# b3_bart_-_rev00.net
KiCad netlist of a schematic drawn in EAGLE
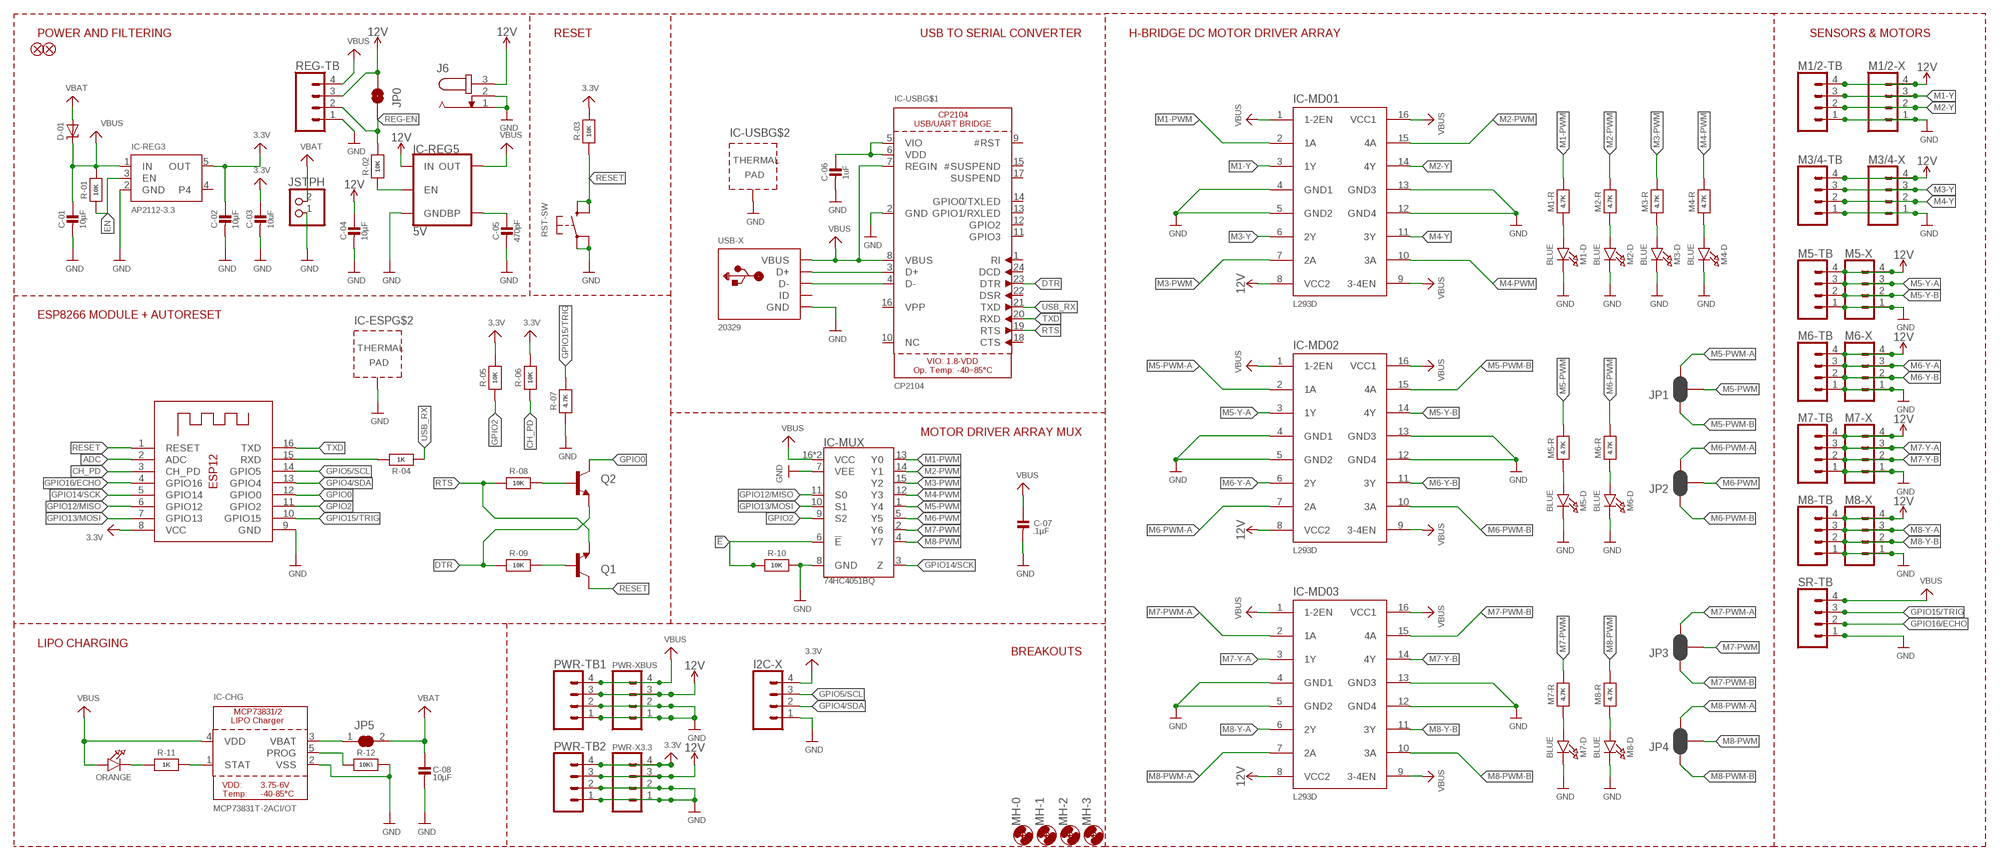
[diagram p0: schematic, sheet 1]

(export (version "E")
  (design (tool "Eeschema 10.0.6"))
  (components
    (comp (ref "C-01")
      (value "10µF")
      (footprint "eagle-import:0805-NO")
      (libsource (lib "eagle-import") (part "CAP_CERAMIC0805-NOOUTLINE"))
    )
    (comp (ref "C-02")
      (value "10µF")
      (footprint "eagle-import:0805-NO")
      (libsource (lib "eagle-import") (part "CAP_CERAMIC0805-NOOUTLINE"))
    )
    (comp (ref "C-03")
      (value "10uF")
      (footprint "eagle-import:0805-NO")
      (libsource (lib "eagle-import") (part "CAP_CERAMIC0805-NOOUTLINE"))
    )
    (comp (ref "C-04")
      (value "10µF")
      (footprint "eagle-import:0805-NO")
      (libsource (lib "eagle-import") (part "CAP_CERAMIC0805-NOOUTLINE"))
    )
    (comp (ref "C-05")
      (value "470pF")
      (footprint "eagle-import:0805-NO")
      (libsource (lib "eagle-import") (part "CAP_CERAMIC0805-NOOUTLINE"))
    )
    (comp (ref "C-06")
      (value "1uF")
      (footprint "eagle-import:0603-NO@1")
      (libsource (lib "eagle-import") (part "CAP_CERAMIC0603_NO"))
    )
    (comp (ref "C-07")
      (value ".1µF")
      (footprint "eagle-import:0805-NO")
      (libsource (lib "eagle-import") (part "CAP_CERAMIC0805-NOOUTLINE"))
    )
    (comp (ref "C-08")
      (value "10µF")
      (footprint "eagle-import:0805-NO")
      (libsource (lib "eagle-import") (part "CAP_CERAMIC0805-NOOUTLINE"))
    )
    (comp (ref "CHG-D")
      (value "ORANGE")
      (footprint "eagle-import:CHIPLED_0805_NOOUTLINE")
      (libsource (lib "eagle-import") (part "LED0805_NOOUTLINE"))
    )
    (comp (ref "D-01")
      (value "MBR120")
      (footprint "eagle-import:SOD-123")
      (libsource (lib "eagle-import") (part "DIODE-SCHOTTKYSOD-123"))
    )
    (comp (ref "FD1")
      (value "FIDUCIAL1X2")
      (footprint "eagle-import:FIDUCIAL-1X2")
      (libsource (lib "eagle-import") (part "FIDUCIAL1X2"))
    )
    (comp (ref "FD2")
      (value "FIDUCIAL1X2")
      (footprint "eagle-import:FIDUCIAL-1X2")
      (libsource (lib "eagle-import") (part "FIDUCIAL1X2"))
    )
    (comp (ref "I2C-X")
      (value "CONN_04LONGPADS")
      (footprint "eagle-import:1X04_LONGPADS")
      (libsource (lib "eagle-import") (part "CONN_04LONGPADS"))
    )
    (comp (ref "IC-CHG")
      (value "MCP73831T-2ACI/OT")
      (footprint "eagle-import:SOT23-5")
      (libsource (lib "eagle-import") (part "MCP73831/2"))
    )
    (comp (ref "IC-ESP")
      (value "ESP-12")
      (footprint "eagle-import:ESP-12S")
      (libsource (lib "eagle-import") (part "ESP-12S"))
    )
    (comp (ref "IC-MD01")
      (value "L293D")
      (footprint "eagle-import:DIL16")
      (libsource (lib "eagle-import") (part "L293D"))
    )
    (comp (ref "IC-MD02")
      (value "L293D")
      (footprint "eagle-import:DIL16")
      (libsource (lib "eagle-import") (part "L293D"))
    )
    (comp (ref "IC-MD03")
      (value "L293D")
      (footprint "eagle-import:DIL16")
      (libsource (lib "eagle-import") (part "L293D"))
    )
    (comp (ref "IC-MUX")
      (value "74HC4051BQ")
      (footprint "eagle-import:DHVQFN-16-2.5X3.5MM")
      (libsource (lib "eagle-import") (part "74HC4051BQ"))
    )
    (comp (ref "IC-REG3")
      (value "AP2112-3.3")
      (footprint "eagle-import:SOT23-5")
      (libsource (lib "eagle-import") (part "VREG_SOT23-5"))
    )
    (comp (ref "IC-REG5")
      (value "5V")
      (footprint "eagle-import:SOT23-5")
      (libsource (lib "eagle-import") (part "V_REG_MIC52055V"))
    )
    (comp (ref "IC-USB")
      (value "CP2104")
      (footprint "eagle-import:QFN24_4MM_SMSC")
      (libsource (lib "eagle-import") (part "CP2104"))
    )
    (comp (ref "J6")
      (value "JACK-PLUG1")
      (footprint "eagle-import:SPC4078")
      (libsource (lib "eagle-import") (part "JACK-PLUG1"))
    )
    (comp (ref "JP0")
      (value "JUMPER-SMT_2_NO_SILK")
      (footprint "eagle-import:SMT-JUMPER_2_NO_SILK")
      (libsource (lib "eagle-import") (part "JUMPER-SMT_2_NO_SILK"))
    )
    (comp (ref "JP1")
      (value "JUMPER-SMT_3_2-NC_PASTE_SILK")
      (footprint "eagle-import:SMT-JUMPER_3_2-NC_PASTE_SILK")
      (libsource (lib "eagle-import") (part "JUMPER-SMT_3_2-NC_PASTE_SILK"))
    )
    (comp (ref "JP2")
      (value "JUMPER-SMT_3_2-NC_PASTE_SILK")
      (footprint "eagle-import:SMT-JUMPER_3_2-NC_PASTE_SILK")
      (libsource (lib "eagle-import") (part "JUMPER-SMT_3_2-NC_PASTE_SILK"))
    )
    (comp (ref "JP3")
      (value "JUMPER-SMT_3_2-NC_PASTE_SILK")
      (footprint "eagle-import:SMT-JUMPER_3_2-NC_PASTE_SILK")
      (libsource (lib "eagle-import") (part "JUMPER-SMT_3_2-NC_PASTE_SILK"))
    )
    (comp (ref "JP4")
      (value "JUMPER-SMT_3_2-NC_PASTE_SILK")
      (footprint "eagle-import:SMT-JUMPER_3_2-NC_PASTE_SILK")
      (libsource (lib "eagle-import") (part "JUMPER-SMT_3_2-NC_PASTE_SILK"))
    )
    (comp (ref "JP5")
      (value "SOLDERJUMPER_CLOSED")
      (footprint "eagle-import:SOLDERJUMPER_CLOSEDWIRE")
      (libsource (lib "eagle-import") (part "SOLDERJUMPER_CLOSED"))
    )
    (comp (ref "M1-D")
      (value "BLUE")
      (footprint "eagle-import:CHIPLED_0805_NOOUTLINE")
      (libsource (lib "eagle-import") (part "LED0805_NOOUTLINE"))
    )
    (comp (ref "M1-R")
      (value "4.7K")
      (footprint "eagle-import:0603-NO")
      (libsource (lib "eagle-import") (part "RESISTOR_0603_NOOUT"))
    )
    (comp (ref "M1/2-TB")
      (value "CONN_04SCREW")
      (footprint "eagle-import:SCREWTERMINAL-3.5MM-4")
      (libsource (lib "eagle-import") (part "CONN_04SCREW"))
    )
    (comp (ref "M1/2-X")
      (value "CONN_04LONGPADS")
      (footprint "eagle-import:1X04_LONGPADS")
      (libsource (lib "eagle-import") (part "CONN_04LONGPADS"))
    )
    (comp (ref "M2-D")
      (value "BLUE")
      (footprint "eagle-import:CHIPLED_0805_NOOUTLINE")
      (libsource (lib "eagle-import") (part "LED0805_NOOUTLINE"))
    )
    (comp (ref "M2-R")
      (value "4.7K")
      (footprint "eagle-import:0603-NO")
      (libsource (lib "eagle-import") (part "RESISTOR_0603_NOOUT"))
    )
    (comp (ref "M3-D")
      (value "BLUE")
      (footprint "eagle-import:CHIPLED_0805_NOOUTLINE")
      (libsource (lib "eagle-import") (part "LED0805_NOOUTLINE"))
    )
    (comp (ref "M3-R")
      (value "4.7K")
      (footprint "eagle-import:0603-NO")
      (libsource (lib "eagle-import") (part "RESISTOR_0603_NOOUT"))
    )
    (comp (ref "M3/4-TB")
      (value "CONN_04SCREW")
      (footprint "eagle-import:SCREWTERMINAL-3.5MM-4")
      (libsource (lib "eagle-import") (part "CONN_04SCREW"))
    )
    (comp (ref "M3/4-X")
      (value "CONN_04LONGPADS")
      (footprint "eagle-import:1X04_LONGPADS")
      (libsource (lib "eagle-import") (part "CONN_04LONGPADS"))
    )
    (comp (ref "M4-D")
      (value "BLUE")
      (footprint "eagle-import:CHIPLED_0805_NOOUTLINE")
      (libsource (lib "eagle-import") (part "LED0805_NOOUTLINE"))
    )
    (comp (ref "M4-R")
      (value "4.7K")
      (footprint "eagle-import:0603-NO")
      (libsource (lib "eagle-import") (part "RESISTOR_0603_NOOUT"))
    )
    (comp (ref "M5-D")
      (value "BLUE")
      (footprint "eagle-import:CHIPLED_0805_NOOUTLINE")
      (libsource (lib "eagle-import") (part "LED0805_NOOUTLINE"))
    )
    (comp (ref "M5-R")
      (value "4.7K")
      (footprint "eagle-import:0603-NO")
      (libsource (lib "eagle-import") (part "RESISTOR_0603_NOOUT"))
    )
    (comp (ref "M5-TB")
      (value "CONN_04SCREW")
      (footprint "eagle-import:SCREWTERMINAL-3.5MM-4")
      (libsource (lib "eagle-import") (part "CONN_04SCREW"))
    )
    (comp (ref "M5-X")
      (value "CONN_04LONGPADS")
      (footprint "eagle-import:1X04_LONGPADS")
      (libsource (lib "eagle-import") (part "CONN_04LONGPADS"))
    )
    (comp (ref "M6-D")
      (value "BLUE")
      (footprint "eagle-import:CHIPLED_0805_NOOUTLINE")
      (libsource (lib "eagle-import") (part "LED0805_NOOUTLINE"))
    )
    (comp (ref "M6-R")
      (value "4.7K")
      (footprint "eagle-import:0603-NO")
      (libsource (lib "eagle-import") (part "RESISTOR_0603_NOOUT"))
    )
    (comp (ref "M6-TB")
      (value "CONN_04SCREW")
      (footprint "eagle-import:SCREWTERMINAL-3.5MM-4")
      (libsource (lib "eagle-import") (part "CONN_04SCREW"))
    )
    (comp (ref "M6-X")
      (value "CONN_04LONGPADS")
      (footprint "eagle-import:1X04_LONGPADS")
      (libsource (lib "eagle-import") (part "CONN_04LONGPADS"))
    )
    (comp (ref "M7-D")
      (value "BLUE")
      (footprint "eagle-import:CHIPLED_0805_NOOUTLINE")
      (libsource (lib "eagle-import") (part "LED0805_NOOUTLINE"))
    )
    (comp (ref "M7-R")
      (value "4.7K")
      (footprint "eagle-import:0603-NO")
      (libsource (lib "eagle-import") (part "RESISTOR_0603_NOOUT"))
    )
    (comp (ref "M7-TB")
      (value "CONN_04SCREW")
      (footprint "eagle-import:SCREWTERMINAL-3.5MM-4")
      (libsource (lib "eagle-import") (part "CONN_04SCREW"))
    )
    (comp (ref "M7-X")
      (value "CONN_04LONGPADS")
      (footprint "eagle-import:1X04_LONGPADS")
      (libsource (lib "eagle-import") (part "CONN_04LONGPADS"))
    )
    (comp (ref "M8-D")
      (value "BLUE")
      (footprint "eagle-import:CHIPLED_0805_NOOUTLINE")
      (libsource (lib "eagle-import") (part "LED0805_NOOUTLINE"))
    )
    (comp (ref "M8-R")
      (value "4.7K")
      (footprint "eagle-import:0603-NO")
      (libsource (lib "eagle-import") (part "RESISTOR_0603_NOOUT"))
    )
    (comp (ref "M8-TB")
      (value "CONN_04SCREW")
      (footprint "eagle-import:SCREWTERMINAL-3.5MM-4")
      (libsource (lib "eagle-import") (part "CONN_04SCREW"))
    )
    (comp (ref "M8-X")
      (value "CONN_04LONGPADS")
      (footprint "eagle-import:1X04_LONGPADS")
      (libsource (lib "eagle-import") (part "CONN_04LONGPADS"))
    )
    (comp (ref "MH-0")
      (value "MOUNT-HOLE3.0")
      (footprint "eagle-import:3,0")
      (libsource (lib "eagle-import") (part "MOUNT-HOLE3.0"))
    )
    (comp (ref "MH-1")
      (value "MOUNT-HOLE3.0")
      (footprint "eagle-import:3,0")
      (libsource (lib "eagle-import") (part "MOUNT-HOLE3.0"))
    )
    (comp (ref "MH-2")
      (value "MOUNT-HOLE3.0")
      (footprint "eagle-import:3,0")
      (libsource (lib "eagle-import") (part "MOUNT-HOLE3.0"))
    )
    (comp (ref "MH-3")
      (value "MOUNT-HOLE3.0")
      (footprint "eagle-import:3,0")
      (libsource (lib "eagle-import") (part "MOUNT-HOLE3.0"))
    )
    (comp (ref "PWR-TB1")
      (value "CONN_04SCREW")
      (footprint "eagle-import:SCREWTERMINAL-3.5MM-4")
      (libsource (lib "eagle-import") (part "CONN_04SCREW"))
    )
    (comp (ref "PWR-TB2")
      (value "CONN_04SCREW")
      (footprint "eagle-import:SCREWTERMINAL-3.5MM-4")
      (libsource (lib "eagle-import") (part "CONN_04SCREW"))
    )
    (comp (ref "PWR-X3.3")
      (value "CONN_04LONGPADS")
      (footprint "eagle-import:1X04_LONGPADS")
      (libsource (lib "eagle-import") (part "CONN_04LONGPADS"))
    )
    (comp (ref "PWR-XBUS")
      (value "CONN_04LONGPADS")
      (footprint "eagle-import:1X04_LONGPADS")
      (libsource (lib "eagle-import") (part "CONN_04LONGPADS"))
    )
    (comp (ref "Q1")
      (value "mmbt2222")
      (footprint "eagle-import:SOT23-3")
      (libsource (lib "eagle-import") (part "TRANSISTOR_NPNSOT23-3"))
    )
    (comp (ref "Q2")
      (value "mmbt2222")
      (footprint "eagle-import:SOT23-3")
      (libsource (lib "eagle-import") (part "TRANSISTOR_NPNSOT23-3"))
    )
    (comp (ref "R-01")
      (value "10K")
      (footprint "eagle-import:0603-NO")
      (libsource (lib "eagle-import") (part "RESISTOR_0603_NOOUT"))
    )
    (comp (ref "R-02")
      (value "10K")
      (footprint "eagle-import:0603-NO")
      (libsource (lib "eagle-import") (part "RESISTOR_0603_NOOUT"))
    )
    (comp (ref "R-03")
      (value "10K")
      (footprint "eagle-import:0603-NO")
      (libsource (lib "eagle-import") (part "RESISTOR_0603_NOOUT"))
    )
    (comp (ref "R-04")
      (value "1K")
      (footprint "eagle-import:_0603MP")
      (libsource (lib "eagle-import") (part "RESISTOR_0603MP"))
    )
    (comp (ref "R-05")
      (value "10K")
      (footprint "eagle-import:0603-NO")
      (libsource (lib "eagle-import") (part "RESISTOR_0603_NOOUT"))
    )
    (comp (ref "R-06")
      (value "10K")
      (footprint "eagle-import:0603-NO")
      (libsource (lib "eagle-import") (part "RESISTOR_0603_NOOUT"))
    )
    (comp (ref "R-07")
      (value "4.7K")
      (footprint "eagle-import:0603-NO")
      (libsource (lib "eagle-import") (part "RESISTOR_0603_NOOUT"))
    )
    (comp (ref "R-08")
      (value "10K")
      (footprint "eagle-import:0603-NO")
      (libsource (lib "eagle-import") (part "RESISTOR_0603_NOOUT"))
    )
    (comp (ref "R-09")
      (value "10K")
      (footprint "eagle-import:0603-NO")
      (libsource (lib "eagle-import") (part "RESISTOR_0603_NOOUT"))
    )
    (comp (ref "R-10")
      (value "10K")
      (footprint "eagle-import:0603-NO")
      (libsource (lib "eagle-import") (part "RESISTOR_0603_NOOUT"))
    )
    (comp (ref "R-11")
      (value "1K")
      (footprint "eagle-import:0603-NO")
      (libsource (lib "eagle-import") (part "RESISTOR_0603_NOOUT"))
    )
    (comp (ref "R-12")
      (value "10K\\")
      (footprint "eagle-import:0603-NO")
      (libsource (lib "eagle-import") (part "RESISTOR_0603_NOOUT"))
    )
    (comp (ref "REG-TB")
      (value "CONN_04SCREW")
      (footprint "eagle-import:SCREWTERMINAL-3.5MM-4")
      (libsource (lib "eagle-import") (part "CONN_04SCREW"))
    )
    (comp (ref "RST-SW")
      (value "KMR2")
      (footprint "eagle-import:BTN_KMR2_4.6X2.8")
      (libsource (lib "eagle-import") (part "SWITCH_TACT_SMT4.6X2.8"))
    )
    (comp (ref "SR-TB")
      (value "CONN_04SCREW")
      (footprint "eagle-import:SCREWTERMINAL-3.5MM-4")
      (libsource (lib "eagle-import") (part "CONN_04SCREW"))
    )
    (comp (ref "USB-X")
      (value "20329")
      (footprint "eagle-import:4UCONN_20329_V2")
      (libsource (lib "eagle-import") (part "USB_MICRO_20329_V2"))
    )
    (comp (ref "X1")
      (value "JSTPH")
      (footprint "eagle-import:JSTPH2")
      (libsource (lib "eagle-import") (part "CON_JST_PH_2PIN"))
    )
  )
  (nets
    (net (code "1") (name "/~{E}") (class "Default")
      (node (ref "IC-MUX") (pin "6") (pinfunction "~{E}_6") (pintype "bidirectional"))
      (node (ref "R-10") (pin "1") (pinfunction "1_1") (pintype "passive"))
    )
    (net (code "2") (name "3.3V") (class "Default")
      (node (ref "C-02") (pin "1") (pinfunction "1_1") (pintype "passive"))
      (node (ref "C-03") (pin "1") (pinfunction "1_1") (pintype "passive"))
      (node (ref "I2C-X") (pin "4") (pinfunction "4_4") (pintype "passive"))
      (node (ref "IC-ESP") (pin "8") (pinfunction "VCC_8") (pintype "power_in"))
      (node (ref "IC-REG3") (pin "5") (pinfunction "OUT_5") (pintype "power_in"))
      (node (ref "PWR-TB2") (pin "4") (pinfunction "4_4") (pintype "passive"))
      (node (ref "PWR-X3.3") (pin "4") (pinfunction "4_4") (pintype "passive"))
      (node (ref "R-03") (pin "2") (pinfunction "2_2") (pintype "passive"))
      (node (ref "R-05") (pin "2") (pinfunction "2_2") (pintype "passive"))
      (node (ref "R-06") (pin "2") (pinfunction "2_2") (pintype "passive"))
    )
    (net (code "3") (name "12V") (class "Default")
      (node (ref "C-04") (pin "1") (pinfunction "1_1") (pintype "passive"))
      (node (ref "IC-MD01") (pin "8") (pinfunction "VCC2_8") (pintype "power_in"))
      (node (ref "IC-MD02") (pin "8") (pinfunction "VCC2_8") (pintype "power_in"))
      (node (ref "IC-MD03") (pin "8") (pinfunction "VCC2_8") (pintype "power_in"))
      (node (ref "IC-REG5") (pin "1") (pinfunction "IN_1") (pintype "input"))
      (node (ref "J6") (pin "3") (pinfunction "3_3") (pintype "passive"))
      (node (ref "JP0") (pin "2") (pinfunction "2_2") (pintype "passive"))
      (node (ref "M1/2-TB") (pin "4") (pinfunction "4_4") (pintype "passive"))
      (node (ref "M1/2-X") (pin "4") (pinfunction "4_4") (pintype "passive"))
      (node (ref "M3/4-TB") (pin "4") (pinfunction "4_4") (pintype "passive"))
      (node (ref "M3/4-X") (pin "4") (pinfunction "4_4") (pintype "passive"))
      (node (ref "M5-TB") (pin "4") (pinfunction "4_4") (pintype "passive"))
      (node (ref "M5-X") (pin "4") (pinfunction "4_4") (pintype "passive"))
      (node (ref "M6-TB") (pin "4") (pinfunction "4_4") (pintype "passive"))
      (node (ref "M6-X") (pin "4") (pinfunction "4_4") (pintype "passive"))
      (node (ref "M7-TB") (pin "4") (pinfunction "4_4") (pintype "passive"))
      (node (ref "M7-X") (pin "4") (pinfunction "4_4") (pintype "passive"))
      (node (ref "M8-TB") (pin "4") (pinfunction "4_4") (pintype "passive"))
      (node (ref "M8-X") (pin "4") (pinfunction "4_4") (pintype "passive"))
      (node (ref "PWR-TB1") (pin "3") (pinfunction "3_3") (pintype "passive"))
      (node (ref "PWR-TB2") (pin "3") (pinfunction "3_3") (pintype "passive"))
      (node (ref "PWR-X3.3") (pin "3") (pinfunction "3_3") (pintype "passive"))
      (node (ref "PWR-XBUS") (pin "3") (pinfunction "3_3") (pintype "passive"))
      (node (ref "REG-TB") (pin "3") (pinfunction "3_3") (pintype "passive"))
    )
    (net (code "4") (name "ADC") (class "Default")
      (node (ref "IC-ESP") (pin "2") (pinfunction "ADC_2") (pintype "passive"))
    )
    (net (code "5") (name "CH_PD") (class "Default")
      (node (ref "IC-ESP") (pin "3") (pinfunction "CH_PD_3") (pintype "input"))
      (node (ref "R-06") (pin "1") (pinfunction "1_1") (pintype "passive"))
    )
    (net (code "6") (name "DTR") (class "Default")
      (node (ref "IC-USB") (pin "23") (pinfunction "DTR_23") (pintype "output"))
      (node (ref "Q2") (pin "2") (pinfunction "E_2") (pintype "passive"))
      (node (ref "R-09") (pin "1") (pinfunction "1_1") (pintype "passive"))
    )
    (net (code "7") (name "EN") (class "Default")
      (node (ref "IC-REG3") (pin "3") (pinfunction "EN_3") (pintype "input"))
      (node (ref "R-01") (pin "1") (pinfunction "1_1") (pintype "passive"))
    )
    (net (code "8") (name "GND") (class "Default")
      (node (ref "C-01") (pin "2") (pinfunction "2_2") (pintype "passive"))
      (node (ref "C-02") (pin "2") (pinfunction "2_2") (pintype "passive"))
      (node (ref "C-03") (pin "2") (pinfunction "2_2") (pintype "passive"))
      (node (ref "C-04") (pin "2") (pinfunction "2_2") (pintype "passive"))
      (node (ref "C-05") (pin "2") (pinfunction "2_2") (pintype "passive"))
      (node (ref "C-06") (pin "2") (pinfunction "2_2") (pintype "passive"))
      (node (ref "C-07") (pin "2") (pinfunction "2_2") (pintype "passive"))
      (node (ref "C-08") (pin "2") (pinfunction "2_2") (pintype "passive"))
      (node (ref "I2C-X") (pin "1") (pinfunction "1_1") (pintype "passive"))
      (node (ref "IC-CHG") (pin "2") (pinfunction "VSS_2") (pintype "power_in"))
      (node (ref "IC-ESP") (pin "9") (pinfunction "GND_9") (pintype "power_in"))
      (node (ref "IC-ESP") (pin "P$1") (pinfunction "TP_P$1") (pintype "power_in"))
      (node (ref "IC-MD01") (pin "12") (pinfunction "GND4_12") (pintype "power_in"))
      (node (ref "IC-MD01") (pin "13") (pinfunction "GND3_13") (pintype "power_in"))
      (node (ref "IC-MD01") (pin "4") (pinfunction "GND1_4") (pintype "power_in"))
      (node (ref "IC-MD01") (pin "5") (pinfunction "GND2_5") (pintype "power_in"))
      (node (ref "IC-MD02") (pin "12") (pinfunction "GND4_12") (pintype "power_in"))
      (node (ref "IC-MD02") (pin "13") (pinfunction "GND3_13") (pintype "power_in"))
      (node (ref "IC-MD02") (pin "4") (pinfunction "GND1_4") (pintype "power_in"))
      (node (ref "IC-MD02") (pin "5") (pinfunction "GND2_5") (pintype "power_in"))
      (node (ref "IC-MD03") (pin "12") (pinfunction "GND4_12") (pintype "power_in"))
      (node (ref "IC-MD03") (pin "13") (pinfunction "GND3_13") (pintype "power_in"))
      (node (ref "IC-MD03") (pin "4") (pinfunction "GND1_4") (pintype "power_in"))
      (node (ref "IC-MD03") (pin "5") (pinfunction "GND2_5") (pintype "power_in"))
      (node (ref "IC-MUX") (pin "7") (pinfunction "VEE_7") (pintype "bidirectional"))
      (node (ref "IC-MUX") (pin "8") (pinfunction "GND_8") (pintype "bidirectional"))
      (node (ref "IC-REG3") (pin "2") (pinfunction "GND_2") (pintype "power_in"))
      (node (ref "IC-REG5") (pin "2") (pinfunction "GND_2") (pintype "input"))
      (node (ref "IC-USB") (pin "2") (pinfunction "GND_2") (pintype "power_in"))
      (node (ref "IC-USB") (pin "THERM") (pinfunction "TP_THERM") (pintype "power_in"))
      (node (ref "J6") (pin "1") (pinfunction "1_1") (pintype "passive"))
      (node (ref "J6") (pin "2") (pinfunction "2_2") (pintype "passive"))
      (node (ref "M1-D") (pin "C") (pinfunction "C_C") (pintype "passive"))
      (node (ref "M1/2-TB") (pin "1") (pinfunction "1_1") (pintype "passive"))
      (node (ref "M1/2-X") (pin "1") (pinfunction "1_1") (pintype "passive"))
      (node (ref "M2-D") (pin "C") (pinfunction "C_C") (pintype "passive"))
      (node (ref "M3-D") (pin "C") (pinfunction "C_C") (pintype "passive"))
      (node (ref "M3/4-TB") (pin "1") (pinfunction "1_1") (pintype "passive"))
      (node (ref "M3/4-X") (pin "1") (pinfunction "1_1") (pintype "passive"))
      (node (ref "M4-D") (pin "C") (pinfunction "C_C") (pintype "passive"))
      (node (ref "M5-D") (pin "C") (pinfunction "C_C") (pintype "passive"))
      (node (ref "M5-TB") (pin "1") (pinfunction "1_1") (pintype "passive"))
      (node (ref "M5-X") (pin "1") (pinfunction "1_1") (pintype "passive"))
      (node (ref "M6-D") (pin "C") (pinfunction "C_C") (pintype "passive"))
      (node (ref "M6-TB") (pin "1") (pinfunction "1_1") (pintype "passive"))
      (node (ref "M6-X") (pin "1") (pinfunction "1_1") (pintype "passive"))
      (node (ref "M7-D") (pin "C") (pinfunction "C_C") (pintype "passive"))
      (node (ref "M7-TB") (pin "1") (pinfunction "1_1") (pintype "passive"))
      (node (ref "M7-X") (pin "1") (pinfunction "1_1") (pintype "passive"))
      (node (ref "M8-D") (pin "C") (pinfunction "C_C") (pintype "passive"))
      (node (ref "M8-TB") (pin "1") (pinfunction "1_1") (pintype "passive"))
      (node (ref "M8-X") (pin "1") (pinfunction "1_1") (pintype "passive"))
      (node (ref "PWR-TB1") (pin "1") (pinfunction "1_1") (pintype "passive"))
      (node (ref "PWR-TB1") (pin "2") (pinfunction "2_2") (pintype "passive"))
      (node (ref "PWR-TB2") (pin "1") (pinfunction "1_1") (pintype "passive"))
      (node (ref "PWR-TB2") (pin "2") (pinfunction "2_2") (pintype "passive"))
      (node (ref "PWR-X3.3") (pin "1") (pinfunction "1_1") (pintype "passive"))
      (node (ref "PWR-X3.3") (pin "2") (pinfunction "2_2") (pintype "passive"))
      (node (ref "PWR-XBUS") (pin "1") (pinfunction "1_1") (pintype "passive"))
      (node (ref "PWR-XBUS") (pin "2") (pinfunction "2_2") (pintype "passive"))
      (node (ref "R-07") (pin "1") (pinfunction "1_1") (pintype "passive"))
      (node (ref "R-10") (pin "2") (pinfunction "2_2") (pintype "passive"))
      (node (ref "R-12") (pin "2") (pinfunction "2_2") (pintype "passive"))
      (node (ref "REG-TB") (pin "1") (pinfunction "1_1") (pintype "passive"))
      (node (ref "RST-SW") (pin "A") (pinfunction "P_A") (pintype "passive"))
      (node (ref "RST-SW") (pin "A'") (pinfunction "P1_A'") (pintype "passive"))
      (node (ref "SR-TB") (pin "1") (pinfunction "1_1") (pintype "passive"))
      (node (ref "USB-X") (pin "BASE@1") (pinfunction "GND_BASE@1") (pintype "power_in"))
      (node (ref "USB-X") (pin "BASE@2") (pinfunction "GND_BASE@2") (pintype "power_in"))
      (node (ref "USB-X") (pin "GND") (pinfunction "GND_GND") (pintype "power_in"))
      (node (ref "USB-X") (pin "SPRT@1") (pinfunction "GND_SPRT@1") (pintype "power_in"))
      (node (ref "USB-X") (pin "SPRT@2") (pinfunction "GND_SPRT@2") (pintype "power_in"))
      (node (ref "USB-X") (pin "SPRT@3") (pinfunction "GND_SPRT@3") (pintype "power_in"))
      (node (ref "USB-X") (pin "SPRT@4") (pinfunction "GND_SPRT@4") (pintype "power_in"))
      (node (ref "X1") (pin "1") (pinfunction "1_1") (pintype "passive"))
    )
    (net (code "9") (name "GPIO0") (class "Default")
      (node (ref "IC-ESP") (pin "12") (pinfunction "GPIO0_12") (pintype "bidirectional"))
      (node (ref "Q2") (pin "3") (pinfunction "C_3") (pintype "passive"))
    )
    (net (code "10") (name "GPIO2") (class "Default")
      (node (ref "IC-ESP") (pin "11") (pinfunction "GPIO2_11") (pintype "bidirectional"))
      (node (ref "IC-MUX") (pin "9") (pinfunction "S2_9") (pintype "bidirectional"))
      (node (ref "R-05") (pin "1") (pinfunction "1_1") (pintype "passive"))
    )
    (net (code "11") (name "GPIO4{slash}SDA") (class "Default")
      (node (ref "I2C-X") (pin "2") (pinfunction "2_2") (pintype "passive"))
      (node (ref "IC-ESP") (pin "13") (pinfunction "GPIO4_13") (pintype "bidirectional"))
    )
    (net (code "12") (name "GPIO5{slash}SCL") (class "Default")
      (node (ref "I2C-X") (pin "3") (pinfunction "3_3") (pintype "passive"))
      (node (ref "IC-ESP") (pin "14") (pinfunction "GPIO5_14") (pintype "bidirectional"))
    )
    (net (code "13") (name "GPIO12{slash}MISO") (class "Default")
      (node (ref "IC-ESP") (pin "6") (pinfunction "GPIO12_6") (pintype "bidirectional"))
      (node (ref "IC-MUX") (pin "11") (pinfunction "S0_11") (pintype "bidirectional"))
    )
    (net (code "14") (name "GPIO13{slash}MOSI") (class "Default")
      (node (ref "IC-ESP") (pin "7") (pinfunction "GPIO13_7") (pintype "bidirectional"))
      (node (ref "IC-MUX") (pin "10") (pinfunction "S1_10") (pintype "bidirectional"))
    )
    (net (code "15") (name "GPIO14{slash}SCK") (class "Default")
      (node (ref "IC-ESP") (pin "5") (pinfunction "GPIO14_5") (pintype "bidirectional"))
      (node (ref "IC-MUX") (pin "3") (pinfunction "Z_3") (pintype "bidirectional"))
    )
    (net (code "16") (name "GPIO15{slash}TRIG") (class "Default")
      (node (ref "IC-ESP") (pin "10") (pinfunction "GPIO15_10") (pintype "bidirectional"))
      (node (ref "R-07") (pin "2") (pinfunction "2_2") (pintype "passive"))
      (node (ref "SR-TB") (pin "3") (pinfunction "3_3") (pintype "passive"))
    )
    (net (code "17") (name "GPIO16{slash}ECHO") (class "Default")
      (node (ref "IC-ESP") (pin "4") (pinfunction "GPIO16_4") (pintype "bidirectional"))
      (node (ref "SR-TB") (pin "2") (pinfunction "2_2") (pintype "passive"))
    )
    (net (code "18") (name "M1-PWM") (class "Default")
      (node (ref "IC-MD01") (pin "2") (pinfunction "1A_2") (pintype "input"))
      (node (ref "IC-MUX") (pin "13") (pinfunction "Y0_13") (pintype "bidirectional"))
      (node (ref "M1-R") (pin "2") (pinfunction "2_2") (pintype "passive"))
    )
    (net (code "19") (name "M1-Y") (class "Default")
      (node (ref "IC-MD01") (pin "3") (pinfunction "1Y_3") (pintype "output"))
      (node (ref "M1/2-TB") (pin "3") (pinfunction "3_3") (pintype "passive"))
      (node (ref "M1/2-X") (pin "3") (pinfunction "3_3") (pintype "passive"))
    )
    (net (code "20") (name "M2-PWM") (class "Default")
      (node (ref "IC-MD01") (pin "15") (pinfunction "4A_15") (pintype "input"))
      (node (ref "IC-MUX") (pin "14") (pinfunction "Y1_14") (pintype "bidirectional"))
      (node (ref "M2-R") (pin "2") (pinfunction "2_2") (pintype "passive"))
    )
    (net (code "21") (name "M2-Y") (class "Default")
      (node (ref "IC-MD01") (pin "14") (pinfunction "4Y_14") (pintype "output"))
      (node (ref "M1/2-TB") (pin "2") (pinfunction "2_2") (pintype "passive"))
      (node (ref "M1/2-X") (pin "2") (pinfunction "2_2") (pintype "passive"))
    )
    (net (code "22") (name "M3-PWM") (class "Default")
      (node (ref "IC-MD01") (pin "7") (pinfunction "2A_7") (pintype "input"))
      (node (ref "IC-MUX") (pin "15") (pinfunction "Y2_15") (pintype "bidirectional"))
      (node (ref "M3-R") (pin "2") (pinfunction "2_2") (pintype "passive"))
    )
    (net (code "23") (name "M3-Y") (class "Default")
      (node (ref "IC-MD01") (pin "6") (pinfunction "2Y_6") (pintype "output"))
      (node (ref "M3/4-TB") (pin "3") (pinfunction "3_3") (pintype "passive"))
      (node (ref "M3/4-X") (pin "3") (pinfunction "3_3") (pintype "passive"))
    )
    (net (code "24") (name "M4-PWM") (class "Default")
      (node (ref "IC-MD01") (pin "10") (pinfunction "3A_10") (pintype "input"))
      (node (ref "IC-MUX") (pin "12") (pinfunction "Y3_12") (pintype "bidirectional"))
      (node (ref "M4-R") (pin "2") (pinfunction "2_2") (pintype "passive"))
    )
    (net (code "25") (name "M4-Y") (class "Default")
      (node (ref "IC-MD01") (pin "11") (pinfunction "3Y_11") (pintype "output"))
      (node (ref "M3/4-TB") (pin "2") (pinfunction "2_2") (pintype "passive"))
      (node (ref "M3/4-X") (pin "2") (pinfunction "2_2") (pintype "passive"))
    )
    (net (code "26") (name "M5-PWM") (class "Default")
      (node (ref "IC-MUX") (pin "1") (pinfunction "Y4_1") (pintype "bidirectional"))
      (node (ref "JP1") (pin "2") (pinfunction "2_2") (pintype "passive"))
      (node (ref "M5-R") (pin "2") (pinfunction "2_2") (pintype "passive"))
    )
    (net (code "27") (name "M5-PWM-A") (class "Default")
      (node (ref "IC-MD02") (pin "2") (pinfunction "1A_2") (pintype "input"))
      (node (ref "JP1") (pin "3") (pinfunction "3_3") (pintype "passive"))
    )
    (net (code "28") (name "M5-PWM-B") (class "Default")
      (node (ref "IC-MD02") (pin "15") (pinfunction "4A_15") (pintype "input"))
      (node (ref "JP1") (pin "1") (pinfunction "1_1") (pintype "passive"))
    )
    (net (code "29") (name "M5-Y-A") (class "Default")
      (node (ref "IC-MD02") (pin "3") (pinfunction "1Y_3") (pintype "output"))
      (node (ref "M5-TB") (pin "3") (pinfunction "3_3") (pintype "passive"))
      (node (ref "M5-X") (pin "3") (pinfunction "3_3") (pintype "passive"))
    )
    (net (code "30") (name "M5-Y-B") (class "Default")
      (node (ref "IC-MD02") (pin "14") (pinfunction "4Y_14") (pintype "output"))
      (node (ref "M5-TB") (pin "2") (pinfunction "2_2") (pintype "passive"))
      (node (ref "M5-X") (pin "2") (pinfunction "2_2") (pintype "passive"))
    )
    (net (code "31") (name "M6-PWM") (class "Default")
      (node (ref "IC-MUX") (pin "5") (pinfunction "Y5_5") (pintype "bidirectional"))
      (node (ref "JP2") (pin "2") (pinfunction "2_2") (pintype "passive"))
      (node (ref "M6-R") (pin "2") (pinfunction "2_2") (pintype "passive"))
    )
    (net (code "32") (name "M6-PWM-A") (class "Default")
      (node (ref "IC-MD02") (pin "7") (pinfunction "2A_7") (pintype "input"))
      (node (ref "JP2") (pin "3") (pinfunction "3_3") (pintype "passive"))
    )
    (net (code "33") (name "M6-PWM-B") (class "Default")
      (node (ref "IC-MD02") (pin "10") (pinfunction "3A_10") (pintype "input"))
      (node (ref "JP2") (pin "1") (pinfunction "1_1") (pintype "passive"))
    )
    (net (code "34") (name "M6-Y-A") (class "Default")
      (node (ref "IC-MD02") (pin "6") (pinfunction "2Y_6") (pintype "output"))
      (node (ref "M6-TB") (pin "3") (pinfunction "3_3") (pintype "passive"))
      (node (ref "M6-X") (pin "3") (pinfunction "3_3") (pintype "passive"))
    )
    (net (code "35") (name "M6-Y-B") (class "Default")
      (node (ref "IC-MD02") (pin "11") (pinfunction "3Y_11") (pintype "output"))
      (node (ref "M6-TB") (pin "2") (pinfunction "2_2") (pintype "passive"))
      (node (ref "M6-X") (pin "2") (pinfunction "2_2") (pintype "passive"))
    )
    (net (code "36") (name "M7-PWM") (class "Default")
      (node (ref "IC-MUX") (pin "2") (pinfunction "Y6_2") (pintype "bidirectional"))
      (node (ref "JP3") (pin "2") (pinfunction "2_2") (pintype "passive"))
      (node (ref "M7-R") (pin "2") (pinfunction "2_2") (pintype "passive"))
    )
    (net (code "37") (name "M7-PWM-A") (class "Default")
      (node (ref "IC-MD03") (pin "2") (pinfunction "1A_2") (pintype "input"))
      (node (ref "JP3") (pin "3") (pinfunction "3_3") (pintype "passive"))
    )
    (net (code "38") (name "M7-PWM-B") (class "Default")
      (node (ref "IC-MD03") (pin "15") (pinfunction "4A_15") (pintype "input"))
      (node (ref "JP3") (pin "1") (pinfunction "1_1") (pintype "passive"))
    )
    (net (code "39") (name "M7-Y-A") (class "Default")
      (node (ref "IC-MD03") (pin "3") (pinfunction "1Y_3") (pintype "output"))
      (node (ref "M7-TB") (pin "3") (pinfunction "3_3") (pintype "passive"))
      (node (ref "M7-X") (pin "3") (pinfunction "3_3") (pintype "passive"))
    )
    (net (code "40") (name "M7-Y-B") (class "Default")
      (node (ref "IC-MD03") (pin "14") (pinfunction "4Y_14") (pintype "output"))
      (node (ref "M7-TB") (pin "2") (pinfunction "2_2") (pintype "passive"))
      (node (ref "M7-X") (pin "2") (pinfunction "2_2") (pintype "passive"))
    )
    (net (code "41") (name "M8-PWM") (class "Default")
      (node (ref "IC-MUX") (pin "4") (pinfunction "Y7_4") (pintype "bidirectional"))
      (node (ref "JP4") (pin "2") (pinfunction "2_2") (pintype "passive"))
      (node (ref "M8-R") (pin "2") (pinfunction "2_2") (pintype "passive"))
    )
    (net (code "42") (name "M8-PWM-A") (class "Default")
      (node (ref "IC-MD03") (pin "7") (pinfunction "2A_7") (pintype "input"))
      (node (ref "JP4") (pin "3") (pinfunction "3_3") (pintype "passive"))
    )
    (net (code "43") (name "M8-PWM-B") (class "Default")
      (node (ref "IC-MD03") (pin "10") (pinfunction "3A_10") (pintype "input"))
      (node (ref "JP4") (pin "1") (pinfunction "1_1") (pintype "passive"))
    )
    (net (code "44") (name "M8-Y-A") (class "Default")
      (node (ref "IC-MD03") (pin "6") (pinfunction "2Y_6") (pintype "output"))
      (node (ref "M8-TB") (pin "3") (pinfunction "3_3") (pintype "passive"))
      (node (ref "M8-X") (pin "3") (pinfunction "3_3") (pintype "passive"))
    )
    (net (code "45") (name "M8-Y-B") (class "Default")
      (node (ref "IC-MD03") (pin "11") (pinfunction "3Y_11") (pintype "output"))
      (node (ref "M8-TB") (pin "2") (pinfunction "2_2") (pintype "passive"))
      (node (ref "M8-X") (pin "2") (pinfunction "2_2") (pintype "passive"))
    )
    (net (code "46") (name "Net-(CHG-D-PadC)") (class "Default")
      (node (ref "CHG-D") (pin "C") (pinfunction "C_C") (pintype "passive"))
      (node (ref "R-11") (pin "1") (pinfunction "1_1") (pintype "passive"))
    )
    (net (code "47") (name "Net-(IC-CHG-PROG)") (class "Default")
      (node (ref "IC-CHG") (pin "5") (pinfunction "PROG_5") (pintype "input"))
      (node (ref "R-12") (pin "1") (pinfunction "1_1") (pintype "passive"))
    )
    (net (code "48") (name "Net-(IC-CHG-STAT)") (class "Default")
      (node (ref "IC-CHG") (pin "1") (pinfunction "STAT_1") (pintype "output"))
      (node (ref "R-11") (pin "2") (pinfunction "2_2") (pintype "passive"))
    )
    (net (code "49") (name "Net-(IC-CHG-VBAT)") (class "Default")
      (node (ref "IC-CHG") (pin "3") (pinfunction "VBAT_3") (pintype "power_in"))
      (node (ref "JP5") (pin "1") (pinfunction "1_1") (pintype "passive"))
    )
    (net (code "50") (name "Net-(IC-ESPA-RXD)") (class "Default")
      (node (ref "IC-ESP") (pin "15") (pinfunction "RXD_15") (pintype "input"))
      (node (ref "R-04") (pin "2") (pinfunction "2_2") (pintype "passive"))
    )
    (net (code "51") (name "Net-(IC-REG5-BP)") (class "Default")
      (node (ref "C-05") (pin "1") (pinfunction "1_1") (pintype "passive"))
      (node (ref "IC-REG5") (pin "4") (pinfunction "BP_4") (pintype "input"))
    )
    (net (code "52") (name "Net-(IC-REG5-EN)") (class "Default")
      (node (ref "IC-REG5") (pin "3") (pinfunction "EN_3") (pintype "input"))
      (node (ref "R-02") (pin "1") (pinfunction "1_1") (pintype "passive"))
    )
    (net (code "53") (name "Net-(IC-USBA-D+)") (class "Default")
      (node (ref "IC-USB") (pin "3") (pinfunction "D+_3") (pintype "bidirectional"))
      (node (ref "USB-X") (pin "D+") (pinfunction "D+_D+") (pintype "bidirectional"))
    )
    (net (code "54") (name "Net-(IC-USBA-D-)") (class "Default")
      (node (ref "IC-USB") (pin "4") (pinfunction "D-_4") (pintype "bidirectional"))
      (node (ref "USB-X") (pin "D-") (pinfunction "D-_D-") (pintype "bidirectional"))
    )
    (net (code "55") (name "Net-(IC-USBA-VDD)") (class "Default")
      (node (ref "C-06") (pin "1") (pinfunction "1_1") (pintype "passive"))
      (node (ref "IC-USB") (pin "5") (pinfunction "VIO_5") (pintype "power_in"))
      (node (ref "IC-USB") (pin "6") (pinfunction "VDD_6") (pintype "power_in"))
    )
    (net (code "56") (name "Net-(M1-D-PadA)") (class "Default")
      (node (ref "M1-D") (pin "A") (pinfunction "A_A") (pintype "passive"))
      (node (ref "M1-R") (pin "1") (pinfunction "1_1") (pintype "passive"))
    )
    (net (code "57") (name "Net-(M2-D-PadA)") (class "Default")
      (node (ref "M2-D") (pin "A") (pinfunction "A_A") (pintype "passive"))
      (node (ref "M2-R") (pin "1") (pinfunction "1_1") (pintype "passive"))
    )
    (net (code "58") (name "Net-(M3-D-PadA)") (class "Default")
      (node (ref "M3-D") (pin "A") (pinfunction "A_A") (pintype "passive"))
      (node (ref "M3-R") (pin "1") (pinfunction "1_1") (pintype "passive"))
    )
    (net (code "59") (name "Net-(M4-D-PadA)") (class "Default")
      (node (ref "M4-D") (pin "A") (pinfunction "A_A") (pintype "passive"))
      (node (ref "M4-R") (pin "1") (pinfunction "1_1") (pintype "passive"))
    )
    (net (code "60") (name "Net-(M5-D-PadA)") (class "Default")
      (node (ref "M5-D") (pin "A") (pinfunction "A_A") (pintype "passive"))
      (node (ref "M5-R") (pin "1") (pinfunction "1_1") (pintype "passive"))
    )
    (net (code "61") (name "Net-(M6-D-PadA)") (class "Default")
      (node (ref "M6-D") (pin "A") (pinfunction "A_A") (pintype "passive"))
      (node (ref "M6-R") (pin "1") (pinfunction "1_1") (pintype "passive"))
    )
    (net (code "62") (name "Net-(M7-D-PadA)") (class "Default")
      (node (ref "M7-D") (pin "A") (pinfunction "A_A") (pintype "passive"))
      (node (ref "M7-R") (pin "1") (pinfunction "1_1") (pintype "passive"))
    )
    (net (code "63") (name "Net-(M8-D-PadA)") (class "Default")
      (node (ref "M8-D") (pin "A") (pinfunction "A_A") (pintype "passive"))
      (node (ref "M8-R") (pin "1") (pinfunction "1_1") (pintype "passive"))
    )
    (net (code "64") (name "Net-(Q1-B)") (class "Default")
      (node (ref "Q1") (pin "1") (pinfunction "B_1") (pintype "passive"))
      (node (ref "R-09") (pin "2") (pinfunction "2_2") (pintype "passive"))
    )
    (net (code "65") (name "Net-(Q2-B)") (class "Default")
      (node (ref "Q2") (pin "1") (pinfunction "B_1") (pintype "passive"))
      (node (ref "R-08") (pin "2") (pinfunction "2_2") (pintype "passive"))
    )
    (net (code "66") (name "REG-EN") (class "Default")
      (node (ref "JP0") (pin "1") (pinfunction "1_1") (pintype "passive"))
      (node (ref "R-02") (pin "2") (pinfunction "2_2") (pintype "passive"))
      (node (ref "REG-TB") (pin "2") (pinfunction "2_2") (pintype "passive"))
    )
    (net (code "67") (name "RESET") (class "Default")
      (node (ref "IC-ESP") (pin "1") (pinfunction "RESET_1") (pintype "input"))
      (node (ref "Q1") (pin "3") (pinfunction "C_3") (pintype "passive"))
      (node (ref "R-03") (pin "1") (pinfunction "1_1") (pintype "passive"))
      (node (ref "RST-SW") (pin "B") (pinfunction "S_B") (pintype "passive"))
      (node (ref "RST-SW") (pin "B'") (pinfunction "S1_B'") (pintype "passive"))
    )
    (net (code "68") (name "RTS") (class "Default")
      (node (ref "IC-USB") (pin "19") (pinfunction "RTS_19") (pintype "output"))
      (node (ref "Q1") (pin "2") (pinfunction "E_2") (pintype "passive"))
      (node (ref "R-08") (pin "1") (pinfunction "1_1") (pintype "passive"))
    )
    (net (code "69") (name "TXD") (class "Default")
      (node (ref "IC-ESP") (pin "16") (pinfunction "TXD_16") (pintype "output"))
      (node (ref "IC-USB") (pin "20") (pinfunction "RXD_20") (pintype "input"))
    )
    (net (code "70") (name "USB_RX") (class "Default")
      (node (ref "IC-USB") (pin "21") (pinfunction "TXD_21") (pintype "output"))
      (node (ref "R-04") (pin "1") (pinfunction "1_1") (pintype "passive"))
    )
    (net (code "71") (name "VBAT") (class "Default")
      (node (ref "C-08") (pin "1") (pinfunction "1_1") (pintype "passive"))
      (node (ref "D-01") (pin "A") (pinfunction "A_A") (pintype "passive"))
      (node (ref "JP5") (pin "2") (pinfunction "2_2") (pintype "passive"))
      (node (ref "X1") (pin "2") (pinfunction "2_2") (pintype "passive"))
    )
    (net (code "72") (name "VBUS") (class "Default")
      (node (ref "C-01") (pin "1") (pinfunction "1_1") (pintype "passive"))
      (node (ref "C-07") (pin "1") (pinfunction "1_1") (pintype "passive"))
      (node (ref "CHG-D") (pin "A") (pinfunction "A_A") (pintype "passive"))
      (node (ref "D-01") (pin "C") (pinfunction "C_C") (pintype "passive"))
      (node (ref "IC-CHG") (pin "4") (pinfunction "VDD_4") (pintype "power_in"))
      (node (ref "IC-MD01") (pin "1") (pinfunction "1-2EN_1") (pintype "input"))
      (node (ref "IC-MD01") (pin "16") (pinfunction "VCC1_16") (pintype "power_in"))
      (node (ref "IC-MD01") (pin "9") (pinfunction "3-4EN_9") (pintype "input"))
      (node (ref "IC-MD02") (pin "1") (pinfunction "1-2EN_1") (pintype "input"))
      (node (ref "IC-MD02") (pin "16") (pinfunction "VCC1_16") (pintype "power_in"))
      (node (ref "IC-MD02") (pin "9") (pinfunction "3-4EN_9") (pintype "input"))
      (node (ref "IC-MD03") (pin "1") (pinfunction "1-2EN_1") (pintype "input"))
      (node (ref "IC-MD03") (pin "16") (pinfunction "VCC1_16") (pintype "power_in"))
      (node (ref "IC-MD03") (pin "9") (pinfunction "3-4EN_9") (pintype "input"))
      (node (ref "IC-MUX") (pin "16") (pinfunction "VCC_16") (pintype "bidirectional"))
      (node (ref "IC-MUX") (pin "EP") (pinfunction "VCC_EP") (pintype "bidirectional"))
      (node (ref "IC-REG3") (pin "1") (pinfunction "IN_1") (pintype "power_in"))
      (node (ref "IC-REG5") (pin "5") (pinfunction "OUT_5") (pintype "passive"))
      (node (ref "IC-USB") (pin "7") (pinfunction "REGIN_7") (pintype "power_in"))
      (node (ref "IC-USB") (pin "8") (pinfunction "VBUS_8") (pintype "power_in"))
      (node (ref "PWR-TB1") (pin "4") (pinfunction "4_4") (pintype "passive"))
      (node (ref "PWR-XBUS") (pin "4") (pinfunction "4_4") (pintype "passive"))
      (node (ref "R-01") (pin "2") (pinfunction "2_2") (pintype "passive"))
      (node (ref "REG-TB") (pin "4") (pinfunction "4_4") (pintype "passive"))
      (node (ref "SR-TB") (pin "4") (pinfunction "4_4") (pintype "passive"))
      (node (ref "USB-X") (pin "VBUS") (pinfunction "VBUS_VBUS") (pintype "power_in"))
    )
    (net (code "73") (name "unconnected-(IC-REG3-P4-Pad4)") (class "Default")
      (node (ref "IC-REG3") (pin "4") (pinfunction "P4_4") (pintype "bidirectional"))
    )
    (net (code "74") (name "unconnected-(IC-USBA-#RST-Pad9)") (class "Default")
      (node (ref "IC-USB") (pin "9") (pinfunction "#RST_9") (pintype "bidirectional"))
    )
    (net (code "75") (name "unconnected-(IC-USBA-#SUSPEND-Pad15)") (class "Default")
      (node (ref "IC-USB") (pin "15") (pinfunction "#SUSPEND_15") (pintype "output"))
    )
    (net (code "76") (name "unconnected-(IC-USBA-CTS-Pad18)") (class "Default")
      (node (ref "IC-USB") (pin "18") (pinfunction "CTS_18") (pintype "input"))
    )
    (net (code "77") (name "unconnected-(IC-USBA-DCD-Pad24)") (class "Default")
      (node (ref "IC-USB") (pin "24") (pinfunction "DCD_24") (pintype "input"))
    )
    (net (code "78") (name "unconnected-(IC-USBA-DSR-Pad22)") (class "Default")
      (node (ref "IC-USB") (pin "22") (pinfunction "DSR_22") (pintype "input"))
    )
    (net (code "79") (name "unconnected-(IC-USBA-GPIO0{slash}TXLED-Pad14)") (class "Default")
      (node (ref "IC-USB") (pin "14") (pinfunction "GPIO0/TXLED_14") (pintype "bidirectional"))
    )
    (net (code "80") (name "unconnected-(IC-USBA-GPIO1{slash}RXLED-Pad13)") (class "Default")
      (node (ref "IC-USB") (pin "13") (pinfunction "GPIO1/RXLED_13") (pintype "bidirectional"))
    )
    (net (code "81") (name "unconnected-(IC-USBA-GPIO2-Pad12)") (class "Default")
      (node (ref "IC-USB") (pin "12") (pinfunction "GPIO2_12") (pintype "bidirectional"))
    )
    (net (code "82") (name "unconnected-(IC-USBA-GPIO3-Pad11)") (class "Default")
      (node (ref "IC-USB") (pin "11") (pinfunction "GPIO3_11") (pintype "bidirectional"))
    )
    (net (code "83") (name "unconnected-(IC-USBA-NC-Pad10)") (class "Default")
      (node (ref "IC-USB") (pin "10") (pinfunction "NC_10") (pintype "no_connect"))
    )
    (net (code "84") (name "unconnected-(IC-USBA-RI-Pad1)") (class "Default")
      (node (ref "IC-USB") (pin "1") (pinfunction "RI_1") (pintype "input"))
    )
    (net (code "85") (name "unconnected-(IC-USBA-SUSPEND-Pad17)") (class "Default")
      (node (ref "IC-USB") (pin "17") (pinfunction "SUSPEND_17") (pintype "output"))
    )
    (net (code "86") (name "unconnected-(IC-USBA-VPP-Pad16)") (class "Default")
      (node (ref "IC-USB") (pin "16") (pinfunction "VPP_16") (pintype "bidirectional"))
    )
    (net (code "87") (name "unconnected-(USB-X-PadID)") (class "Default")
      (node (ref "USB-X") (pin "ID") (pinfunction "ID_ID") (pintype "bidirectional"))
    )
  )
)
